# D14_1_0.net
KiCad netlist of a schematic drawn in EAGLE
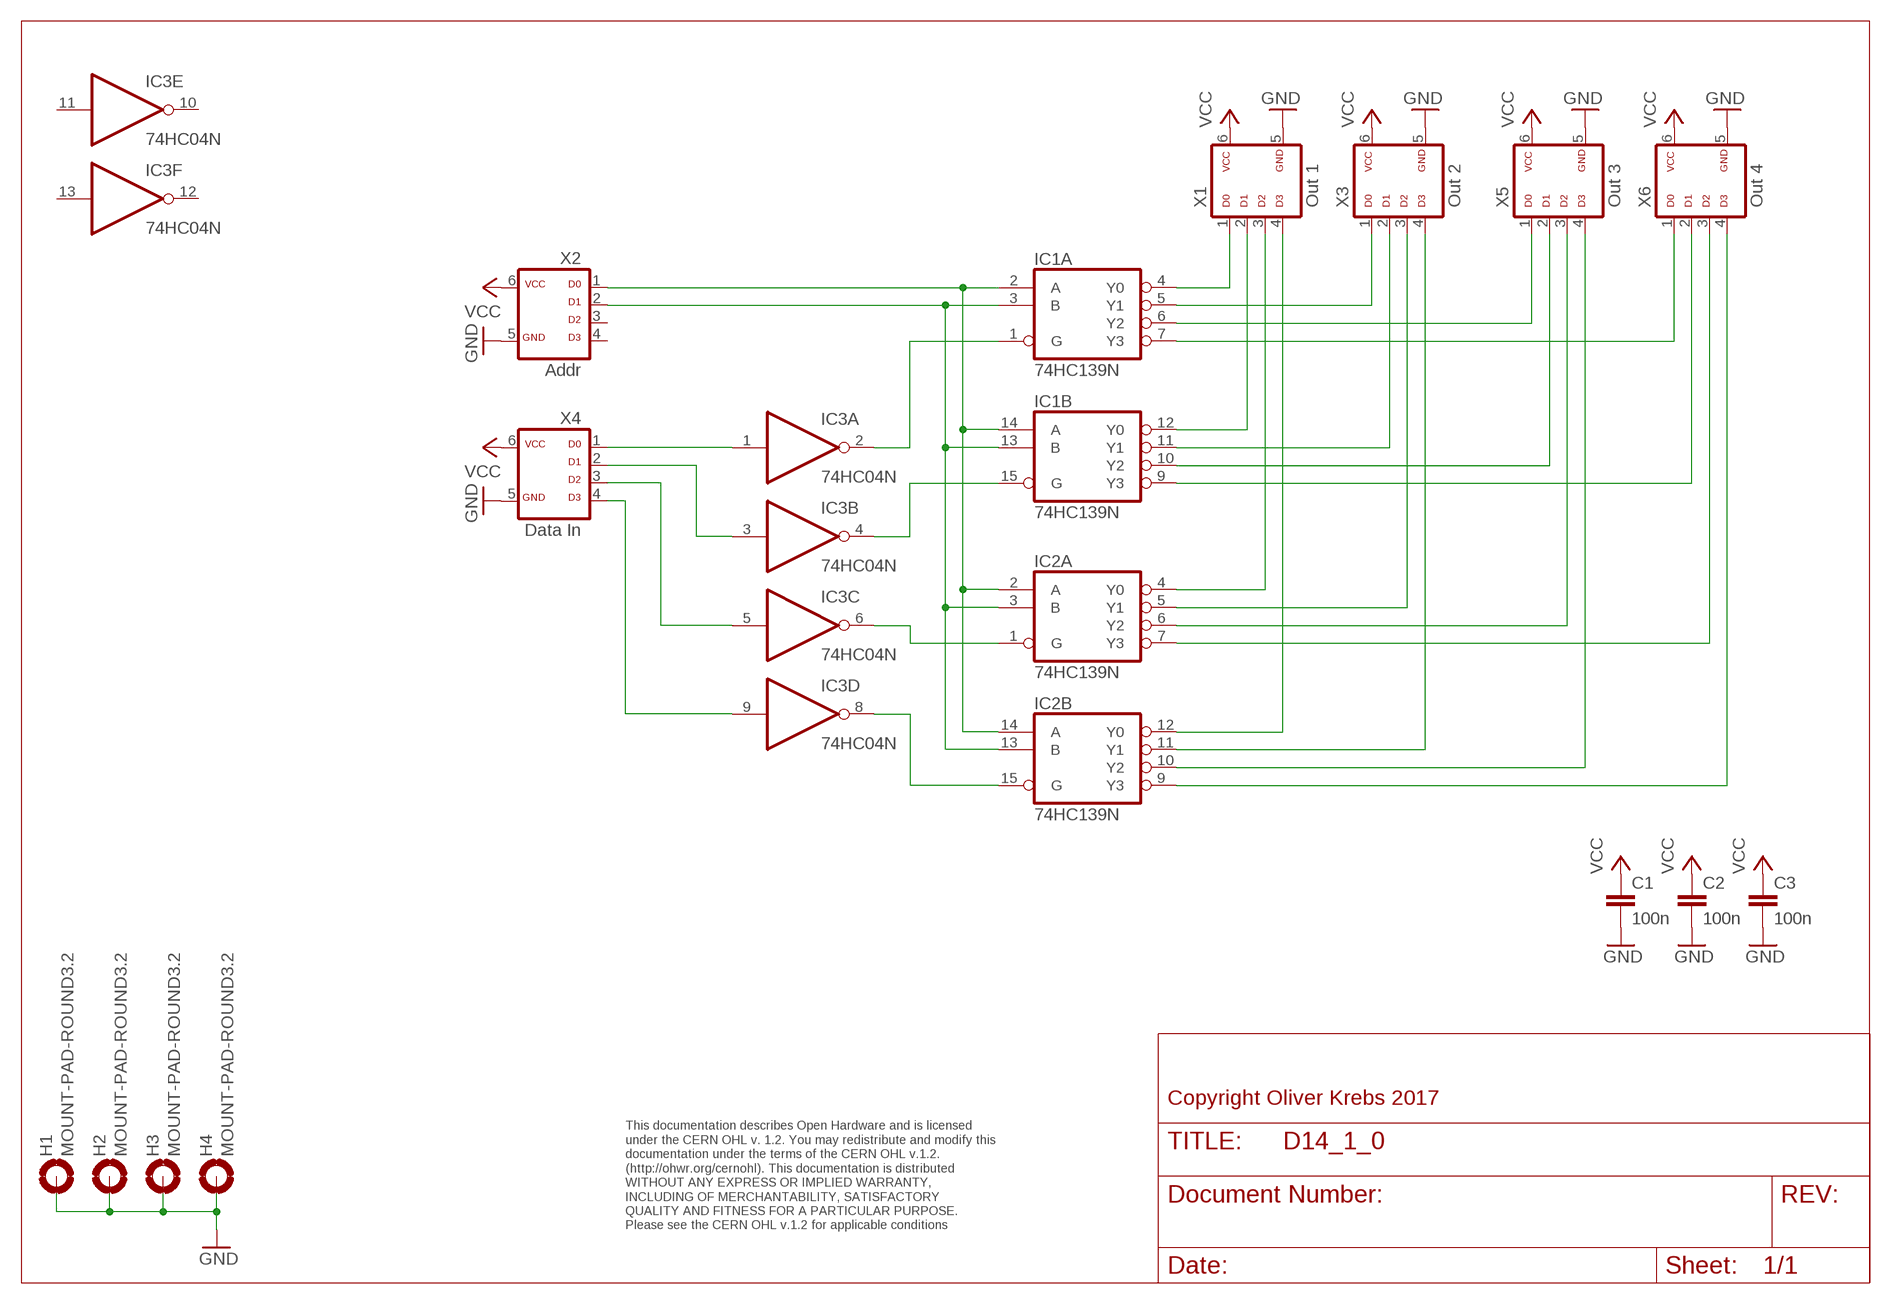
[diagram p0: schematic, sheet 1]

(export (version "E")
  (design (tool "Eeschema 10.0.6"))
  (components
    (comp (ref "C1")
      (value "100n")
      (footprint "eagle-import:C050-025X075")
      (libsource (lib "eagle-import") (part "C-EU050-025X075"))
    )
    (comp (ref "C2")
      (value "100n")
      (footprint "eagle-import:C050-025X075")
      (libsource (lib "eagle-import") (part "C-EU050-025X075"))
    )
    (comp (ref "C3")
      (value "100n")
      (footprint "eagle-import:C050-025X075")
      (libsource (lib "eagle-import") (part "C-EU050-025X075"))
    )
    (comp (ref "H1")
      (value "MOUNT-PAD-ROUND3.2")
      (footprint "eagle-import:3,2-PAD")
      (libsource (lib "eagle-import") (part "MOUNT-PAD-ROUND3.2"))
    )
    (comp (ref "H2")
      (value "MOUNT-PAD-ROUND3.2")
      (footprint "eagle-import:3,2-PAD")
      (libsource (lib "eagle-import") (part "MOUNT-PAD-ROUND3.2"))
    )
    (comp (ref "H3")
      (value "MOUNT-PAD-ROUND3.2")
      (footprint "eagle-import:3,2-PAD")
      (libsource (lib "eagle-import") (part "MOUNT-PAD-ROUND3.2"))
    )
    (comp (ref "H4")
      (value "MOUNT-PAD-ROUND3.2")
      (footprint "eagle-import:3,2-PAD")
      (libsource (lib "eagle-import") (part "MOUNT-PAD-ROUND3.2"))
    )
    (comp (ref "IC1")
      (value "74HC139N")
      (footprint "eagle-import:DIL16")
      (libsource (lib "eagle-import") (part "74139NHC"))
    )
    (comp (ref "IC2")
      (value "74HC139N")
      (footprint "eagle-import:DIL16")
      (libsource (lib "eagle-import") (part "74139NHC"))
    )
    (comp (ref "IC3")
      (value "74HC04N")
      (footprint "eagle-import:DIL14")
      (libsource (lib "eagle-import") (part "7404NHC"))
    )
    (comp (ref "X1")
      (value "Out 1")
      (footprint "eagle-import:ML-6")
      (libsource (lib "eagle-import") (part "ML6D"))
    )
    (comp (ref "X2")
      (value "Addr")
      (footprint "eagle-import:ML-6")
      (libsource (lib "eagle-import") (part "ML6D"))
    )
    (comp (ref "X3")
      (value "Out 2")
      (footprint "eagle-import:ML-6")
      (libsource (lib "eagle-import") (part "ML6D"))
    )
    (comp (ref "X4")
      (value "Data In")
      (footprint "eagle-import:ML-6")
      (libsource (lib "eagle-import") (part "ML6D"))
    )
    (comp (ref "X5")
      (value "Out 3")
      (footprint "eagle-import:ML-6")
      (libsource (lib "eagle-import") (part "ML6D"))
    )
    (comp (ref "X6")
      (value "Out 4")
      (footprint "eagle-import:ML-6")
      (libsource (lib "eagle-import") (part "ML6D"))
    )
  )
  (nets
    (net (code "1") (name "GND") (class "Default")
      (node (ref "C1") (pin "2") (pinfunction "2_2") (pintype "passive"))
      (node (ref "C2") (pin "2") (pinfunction "2_2") (pintype "passive"))
      (node (ref "C3") (pin "2") (pinfunction "2_2") (pintype "passive"))
      (node (ref "H1") (pin "B3,2") (pinfunction "MOUNT_B3,2") (pintype "passive"))
      (node (ref "H2") (pin "B3,2") (pinfunction "MOUNT_B3,2") (pintype "passive"))
      (node (ref "H3") (pin "B3,2") (pinfunction "MOUNT_B3,2") (pintype "passive"))
      (node (ref "H4") (pin "B3,2") (pinfunction "MOUNT_B3,2") (pintype "passive"))
      (node (ref "X1") (pin "5") (pinfunction "5_5") (pintype "passive"))
      (node (ref "X2") (pin "5") (pinfunction "5_5") (pintype "passive"))
      (node (ref "X3") (pin "5") (pinfunction "5_5") (pintype "passive"))
      (node (ref "X4") (pin "5") (pinfunction "5_5") (pintype "passive"))
      (node (ref "X5") (pin "5") (pinfunction "5_5") (pintype "passive"))
      (node (ref "X6") (pin "5") (pinfunction "5_5") (pintype "passive"))
    )
    (net (code "2") (name "Net-(IC1A-A)") (class "Default")
      (node (ref "IC1") (pin "14") (pinfunction "A_14") (pintype "input"))
      (node (ref "IC1") (pin "2") (pinfunction "A_2") (pintype "input"))
      (node (ref "IC2") (pin "14") (pinfunction "A_14") (pintype "input"))
      (node (ref "IC2") (pin "2") (pinfunction "A_2") (pintype "input"))
      (node (ref "X2") (pin "1") (pinfunction "1_1") (pintype "passive"))
    )
    (net (code "3") (name "Net-(IC1A-B)") (class "Default")
      (node (ref "IC1") (pin "13") (pinfunction "B_13") (pintype "input"))
      (node (ref "IC1") (pin "3") (pinfunction "B_3") (pintype "input"))
      (node (ref "IC2") (pin "13") (pinfunction "B_13") (pintype "input"))
      (node (ref "IC2") (pin "3") (pinfunction "B_3") (pintype "input"))
      (node (ref "X2") (pin "2") (pinfunction "2_2") (pintype "passive"))
    )
    (net (code "4") (name "Net-(IC1A-G)") (class "Default")
      (node (ref "IC1") (pin "1") (pinfunction "G_1") (pintype "input"))
      (node (ref "IC3") (pin "2") (pinfunction "O_2") (pintype "output"))
    )
    (net (code "5") (name "Net-(IC1A-Y0)") (class "Default")
      (node (ref "IC1") (pin "4") (pinfunction "Y0_4") (pintype "output"))
      (node (ref "X1") (pin "1") (pinfunction "1_1") (pintype "passive"))
    )
    (net (code "6") (name "Net-(IC1A-Y1)") (class "Default")
      (node (ref "IC1") (pin "5") (pinfunction "Y1_5") (pintype "output"))
      (node (ref "X3") (pin "1") (pinfunction "1_1") (pintype "passive"))
    )
    (net (code "7") (name "Net-(IC1A-Y2)") (class "Default")
      (node (ref "IC1") (pin "6") (pinfunction "Y2_6") (pintype "output"))
      (node (ref "X5") (pin "1") (pinfunction "1_1") (pintype "passive"))
    )
    (net (code "8") (name "Net-(IC1A-Y3)") (class "Default")
      (node (ref "IC1") (pin "7") (pinfunction "Y3_7") (pintype "output"))
      (node (ref "X6") (pin "1") (pinfunction "1_1") (pintype "passive"))
    )
    (net (code "9") (name "Net-(IC1B-G)") (class "Default")
      (node (ref "IC1") (pin "15") (pinfunction "G_15") (pintype "input"))
      (node (ref "IC3") (pin "4") (pinfunction "O_4") (pintype "output"))
    )
    (net (code "10") (name "Net-(IC1B-Y0)") (class "Default")
      (node (ref "IC1") (pin "12") (pinfunction "Y0_12") (pintype "output"))
      (node (ref "X1") (pin "2") (pinfunction "2_2") (pintype "passive"))
    )
    (net (code "11") (name "Net-(IC1B-Y1)") (class "Default")
      (node (ref "IC1") (pin "11") (pinfunction "Y1_11") (pintype "output"))
      (node (ref "X3") (pin "2") (pinfunction "2_2") (pintype "passive"))
    )
    (net (code "12") (name "Net-(IC1B-Y2)") (class "Default")
      (node (ref "IC1") (pin "10") (pinfunction "Y2_10") (pintype "output"))
      (node (ref "X5") (pin "2") (pinfunction "2_2") (pintype "passive"))
    )
    (net (code "13") (name "Net-(IC1B-Y3)") (class "Default")
      (node (ref "IC1") (pin "9") (pinfunction "Y3_9") (pintype "output"))
      (node (ref "X6") (pin "2") (pinfunction "2_2") (pintype "passive"))
    )
    (net (code "14") (name "Net-(IC2A-G)") (class "Default")
      (node (ref "IC2") (pin "1") (pinfunction "G_1") (pintype "input"))
      (node (ref "IC3") (pin "6") (pinfunction "O_6") (pintype "output"))
    )
    (net (code "15") (name "Net-(IC2A-Y0)") (class "Default")
      (node (ref "IC2") (pin "4") (pinfunction "Y0_4") (pintype "output"))
      (node (ref "X1") (pin "3") (pinfunction "3_3") (pintype "passive"))
    )
    (net (code "16") (name "Net-(IC2A-Y1)") (class "Default")
      (node (ref "IC2") (pin "5") (pinfunction "Y1_5") (pintype "output"))
      (node (ref "X3") (pin "3") (pinfunction "3_3") (pintype "passive"))
    )
    (net (code "17") (name "Net-(IC2A-Y2)") (class "Default")
      (node (ref "IC2") (pin "6") (pinfunction "Y2_6") (pintype "output"))
      (node (ref "X5") (pin "3") (pinfunction "3_3") (pintype "passive"))
    )
    (net (code "18") (name "Net-(IC2A-Y3)") (class "Default")
      (node (ref "IC2") (pin "7") (pinfunction "Y3_7") (pintype "output"))
      (node (ref "X6") (pin "3") (pinfunction "3_3") (pintype "passive"))
    )
    (net (code "19") (name "Net-(IC2B-G)") (class "Default")
      (node (ref "IC2") (pin "15") (pinfunction "G_15") (pintype "input"))
      (node (ref "IC3") (pin "8") (pinfunction "O_8") (pintype "output"))
    )
    (net (code "20") (name "Net-(IC2B-Y0)") (class "Default")
      (node (ref "IC2") (pin "12") (pinfunction "Y0_12") (pintype "output"))
      (node (ref "X1") (pin "4") (pinfunction "4_4") (pintype "passive"))
    )
    (net (code "21") (name "Net-(IC2B-Y1)") (class "Default")
      (node (ref "IC2") (pin "11") (pinfunction "Y1_11") (pintype "output"))
      (node (ref "X3") (pin "4") (pinfunction "4_4") (pintype "passive"))
    )
    (net (code "22") (name "Net-(IC2B-Y2)") (class "Default")
      (node (ref "IC2") (pin "10") (pinfunction "Y2_10") (pintype "output"))
      (node (ref "X5") (pin "4") (pinfunction "4_4") (pintype "passive"))
    )
    (net (code "23") (name "Net-(IC2B-Y3)") (class "Default")
      (node (ref "IC2") (pin "9") (pinfunction "Y3_9") (pintype "output"))
      (node (ref "X6") (pin "4") (pinfunction "4_4") (pintype "passive"))
    )
    (net (code "24") (name "Net-(IC3A-I)") (class "Default")
      (node (ref "IC3") (pin "1") (pinfunction "I_1") (pintype "input"))
      (node (ref "X4") (pin "1") (pinfunction "1_1") (pintype "passive"))
    )
    (net (code "25") (name "Net-(IC3B-I)") (class "Default")
      (node (ref "IC3") (pin "3") (pinfunction "I_3") (pintype "input"))
      (node (ref "X4") (pin "2") (pinfunction "2_2") (pintype "passive"))
    )
    (net (code "26") (name "Net-(IC3C-I)") (class "Default")
      (node (ref "IC3") (pin "5") (pinfunction "I_5") (pintype "input"))
      (node (ref "X4") (pin "3") (pinfunction "3_3") (pintype "passive"))
    )
    (net (code "27") (name "Net-(IC3D-I)") (class "Default")
      (node (ref "IC3") (pin "9") (pinfunction "I_9") (pintype "input"))
      (node (ref "X4") (pin "4") (pinfunction "4_4") (pintype "passive"))
    )
    (net (code "28") (name "VCC") (class "Default")
      (node (ref "C1") (pin "1") (pinfunction "1_1") (pintype "passive"))
      (node (ref "C2") (pin "1") (pinfunction "1_1") (pintype "passive"))
      (node (ref "C3") (pin "1") (pinfunction "1_1") (pintype "passive"))
      (node (ref "X1") (pin "6") (pinfunction "6_6") (pintype "passive"))
      (node (ref "X2") (pin "6") (pinfunction "6_6") (pintype "passive"))
      (node (ref "X3") (pin "6") (pinfunction "6_6") (pintype "passive"))
      (node (ref "X4") (pin "6") (pinfunction "6_6") (pintype "passive"))
      (node (ref "X5") (pin "6") (pinfunction "6_6") (pintype "passive"))
      (node (ref "X6") (pin "6") (pinfunction "6_6") (pintype "passive"))
    )
    (net (code "29") (name "unconnected-(IC3E-I-Pad11)") (class "Default")
      (node (ref "IC3") (pin "11") (pinfunction "I_11") (pintype "input"))
    )
    (net (code "30") (name "unconnected-(IC3E-O-Pad10)") (class "Default")
      (node (ref "IC3") (pin "10") (pinfunction "O_10") (pintype "output"))
    )
    (net (code "31") (name "unconnected-(IC3F-I-Pad13)") (class "Default")
      (node (ref "IC3") (pin "13") (pinfunction "I_13") (pintype "input"))
    )
    (net (code "32") (name "unconnected-(IC3F-O-Pad12)") (class "Default")
      (node (ref "IC3") (pin "12") (pinfunction "O_12") (pintype "output"))
    )
    (net (code "33") (name "unconnected-(X2-Pad3)") (class "Default")
      (node (ref "X2") (pin "3") (pinfunction "3_3") (pintype "passive"))
    )
    (net (code "34") (name "unconnected-(X2-Pad4)") (class "Default")
      (node (ref "X2") (pin "4") (pinfunction "4_4") (pintype "passive"))
    )
  )
)
